# l6.net
KiCad netlist of a schematic drawn in Altium Designer
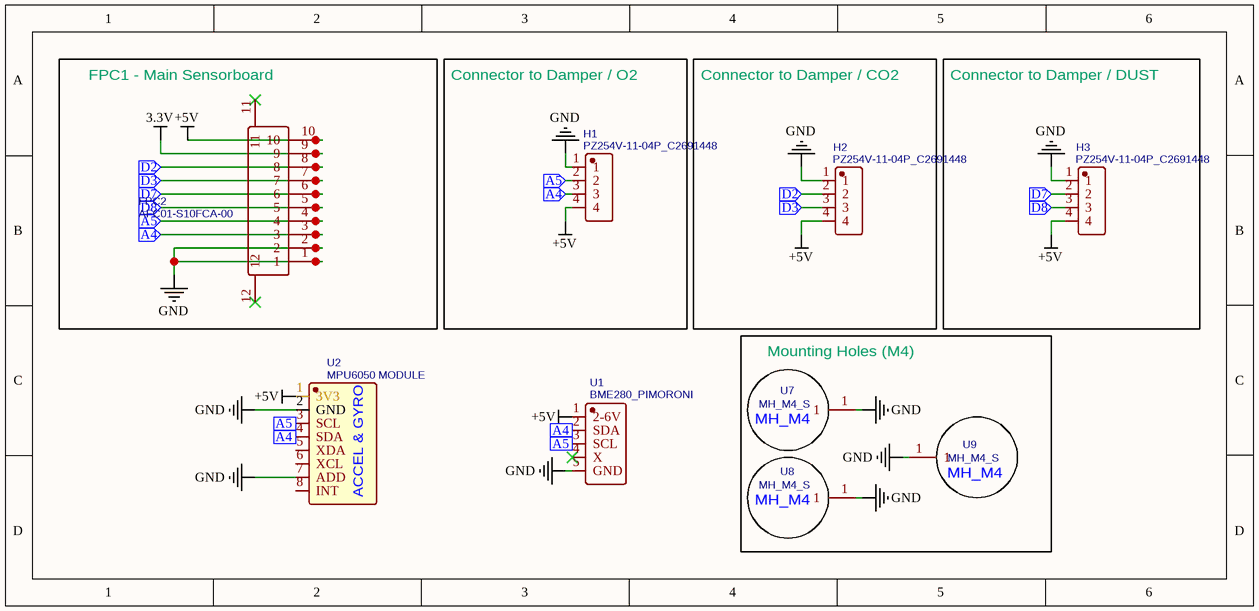
[diagram p0: l6.schdoc]

(export (version "E")
  (design (tool "Eeschema 10.0.6"))
  (components
    (comp (ref "FPC2")
      (value "AFC01-S10FCA-00")
      (fields (field (name "MANUFACTURER") "JS(钜硕电子)") (field (name "CONTRIBUTOR") "LCSC"))
      (libsource (lib "altium-import") (part "root_2_AFC01-S10FCA-00_"))
    )
    (comp (ref "H1")
      (value "PZ254V-11-04P_C2691448")
      (fields
        (field (name "MANUFACTURER") "XFCN(兴飞)")
        (field (name "MANUFACTURER PART") "PZ254V-11-04P")
        (field (name "CONTRIBUTOR") "LCSC")
      )
      (libsource (lib "altium-import") (part "root_0_PZ254V-11-04P_C2691448_"))
    )
    (comp (ref "H2")
      (value "PZ254V-11-04P_C2691448")
      (fields
        (field (name "MANUFACTURER") "XFCN(兴飞)")
        (field (name "MANUFACTURER PART") "PZ254V-11-04P")
        (field (name "CONTRIBUTOR") "LCSC")
      )
      (libsource (lib "altium-import") (part "root_0_PZ254V-11-04P_C2691448_"))
    )
    (comp (ref "H3")
      (value "PZ254V-11-04P_C2691448")
      (fields
        (field (name "MANUFACTURER") "XFCN(兴飞)")
        (field (name "MANUFACTURER PART") "PZ254V-11-04P")
        (field (name "CONTRIBUTOR") "LCSC")
      )
      (libsource (lib "altium-import") (part "root_0_PZ254V-11-04P_C2691448_"))
    )
    (comp (ref "U1")
      (value "BME280_PIMORONI")
      (fields
        (field (name "MANUFACTURER") "ReliaPro")
        (field (name "MANUFACTURER PART") "2.54mm 1*5P Header")
        (field (name "CONTRIBUTOR") "axelvendeville.v2")
      )
      (libsource (lib "altium-import") (part "root_0_BME280_PIMORONI_"))
    )
    (comp (ref "U2")
      (value "MPU6050 MODULE")
      (fields (field (name "MANUFACTURER PART") "MPU6050") (field (name "CONTRIBUTOR") "jofenix"))
      (libsource (lib "altium-import") (part "root_0_MPU6050 MODULE_"))
    )
    (comp (ref "U7")
      (value "MH_M4_S")
      (fields (field (name "CONTRIBUTOR") "js314dev"))
      (libsource (lib "altium-import") (part "root_0_MH_M4_S_"))
    )
    (comp (ref "U8")
      (value "MH_M4_S")
      (fields (field (name "CONTRIBUTOR") "js314dev"))
      (libsource (lib "altium-import") (part "root_0_MH_M4_S_"))
    )
    (comp (ref "U9")
      (value "MH_M4_S")
      (fields (field (name "CONTRIBUTOR") "js314dev"))
      (libsource (lib "altium-import") (part "root_2_MH_M4_S_"))
    )
  )
  (nets
    (net (code "1") (name "+5V") (class "Default")
      (node (ref "FPC2") (pin "10") (pinfunction "10_10") (pintype "passive"))
      (node (ref "H1") (pin "4") (pinfunction "4_4") (pintype "passive"))
      (node (ref "H2") (pin "4") (pinfunction "4_4") (pintype "passive"))
      (node (ref "H3") (pin "4") (pinfunction "4_4") (pintype "passive"))
      (node (ref "U1") (pin "1") (pinfunction "2-6V_1") (pintype "passive"))
      (node (ref "U2") (pin "1") (pinfunction "3V3_1") (pintype "passive"))
    )
    (net (code "2") (name "/A4") (class "Default")
      (node (ref "FPC2") (pin "3") (pinfunction "3_3") (pintype "passive"))
      (node (ref "H1") (pin "3") (pinfunction "3_3") (pintype "passive"))
      (node (ref "U1") (pin "2") (pinfunction "SDA_2") (pintype "passive"))
      (node (ref "U2") (pin "4") (pinfunction "SDA_4") (pintype "passive"))
    )
    (net (code "3") (name "/A5") (class "Default")
      (node (ref "FPC2") (pin "4") (pinfunction "4_4") (pintype "passive"))
      (node (ref "H1") (pin "2") (pinfunction "2_2") (pintype "passive"))
      (node (ref "U1") (pin "3") (pinfunction "SCL_3") (pintype "passive"))
      (node (ref "U2") (pin "3") (pinfunction "SCL_3") (pintype "passive"))
    )
    (net (code "4") (name "/D2") (class "Default")
      (node (ref "FPC2") (pin "8") (pinfunction "8_8") (pintype "passive"))
      (node (ref "H2") (pin "2") (pinfunction "2_2") (pintype "passive"))
    )
    (net (code "5") (name "/D3") (class "Default")
      (node (ref "FPC2") (pin "7") (pinfunction "7_7") (pintype "passive"))
      (node (ref "H2") (pin "3") (pinfunction "3_3") (pintype "passive"))
    )
    (net (code "6") (name "/D7") (class "Default")
      (node (ref "FPC2") (pin "6") (pinfunction "6_6") (pintype "passive"))
      (node (ref "H3") (pin "2") (pinfunction "2_2") (pintype "passive"))
    )
    (net (code "7") (name "/D8") (class "Default")
      (node (ref "FPC2") (pin "5") (pinfunction "5_5") (pintype "passive"))
      (node (ref "H3") (pin "3") (pinfunction "3_3") (pintype "passive"))
    )
    (net (code "8") (name "3.3V") (class "Default")
      (node (ref "FPC2") (pin "9") (pinfunction "9_9") (pintype "passive"))
    )
    (net (code "9") (name "GND") (class "Default")
      (node (ref "FPC2") (pin "1") (pinfunction "1_1") (pintype "passive"))
      (node (ref "FPC2") (pin "2") (pinfunction "2_2") (pintype "passive"))
      (node (ref "H1") (pin "1") (pinfunction "1_1") (pintype "passive"))
      (node (ref "H2") (pin "1") (pinfunction "1_1") (pintype "passive"))
      (node (ref "H3") (pin "1") (pinfunction "1_1") (pintype "passive"))
      (node (ref "U1") (pin "5") (pinfunction "GND_5") (pintype "passive"))
      (node (ref "U2") (pin "2") (pinfunction "GND_2") (pintype "passive"))
      (node (ref "U2") (pin "7") (pinfunction "ADD_7") (pintype "passive"))
      (node (ref "U7") (pin "1") (pinfunction "1_1") (pintype "passive"))
      (node (ref "U8") (pin "1") (pinfunction "1_1") (pintype "passive"))
      (node (ref "U9") (pin "1") (pinfunction "1_1") (pintype "passive"))
    )
    (net (code "10") (name "unconnected-(FPC2-Pad11)") (class "Default")
      (node (ref "FPC2") (pin "11") (pinfunction "11_11") (pintype "passive+no_connect"))
    )
    (net (code "11") (name "unconnected-(FPC2-Pad12)") (class "Default")
      (node (ref "FPC2") (pin "12") (pinfunction "12_12") (pintype "passive+no_connect"))
    )
    (net (code "12") (name "unconnected-(U1-X-Pad4)") (class "Default")
      (node (ref "U1") (pin "4") (pinfunction "X_4") (pintype "passive+no_connect"))
    )
    (net (code "13") (name "unconnected-(U2-INT-Pad8)") (class "Default")
      (node (ref "U2") (pin "8") (pinfunction "INT_8") (pintype "passive"))
    )
    (net (code "14") (name "unconnected-(U2-XCL-Pad6)") (class "Default")
      (node (ref "U2") (pin "6") (pinfunction "XCL_6") (pintype "passive"))
    )
    (net (code "15") (name "unconnected-(U2-XDA-Pad5)") (class "Default")
      (node (ref "U2") (pin "5") (pinfunction "XDA_5") (pintype "passive"))
    )
  )
)
